# Sheet3.net
KiCad netlist of a schematic drawn in Altium Designer
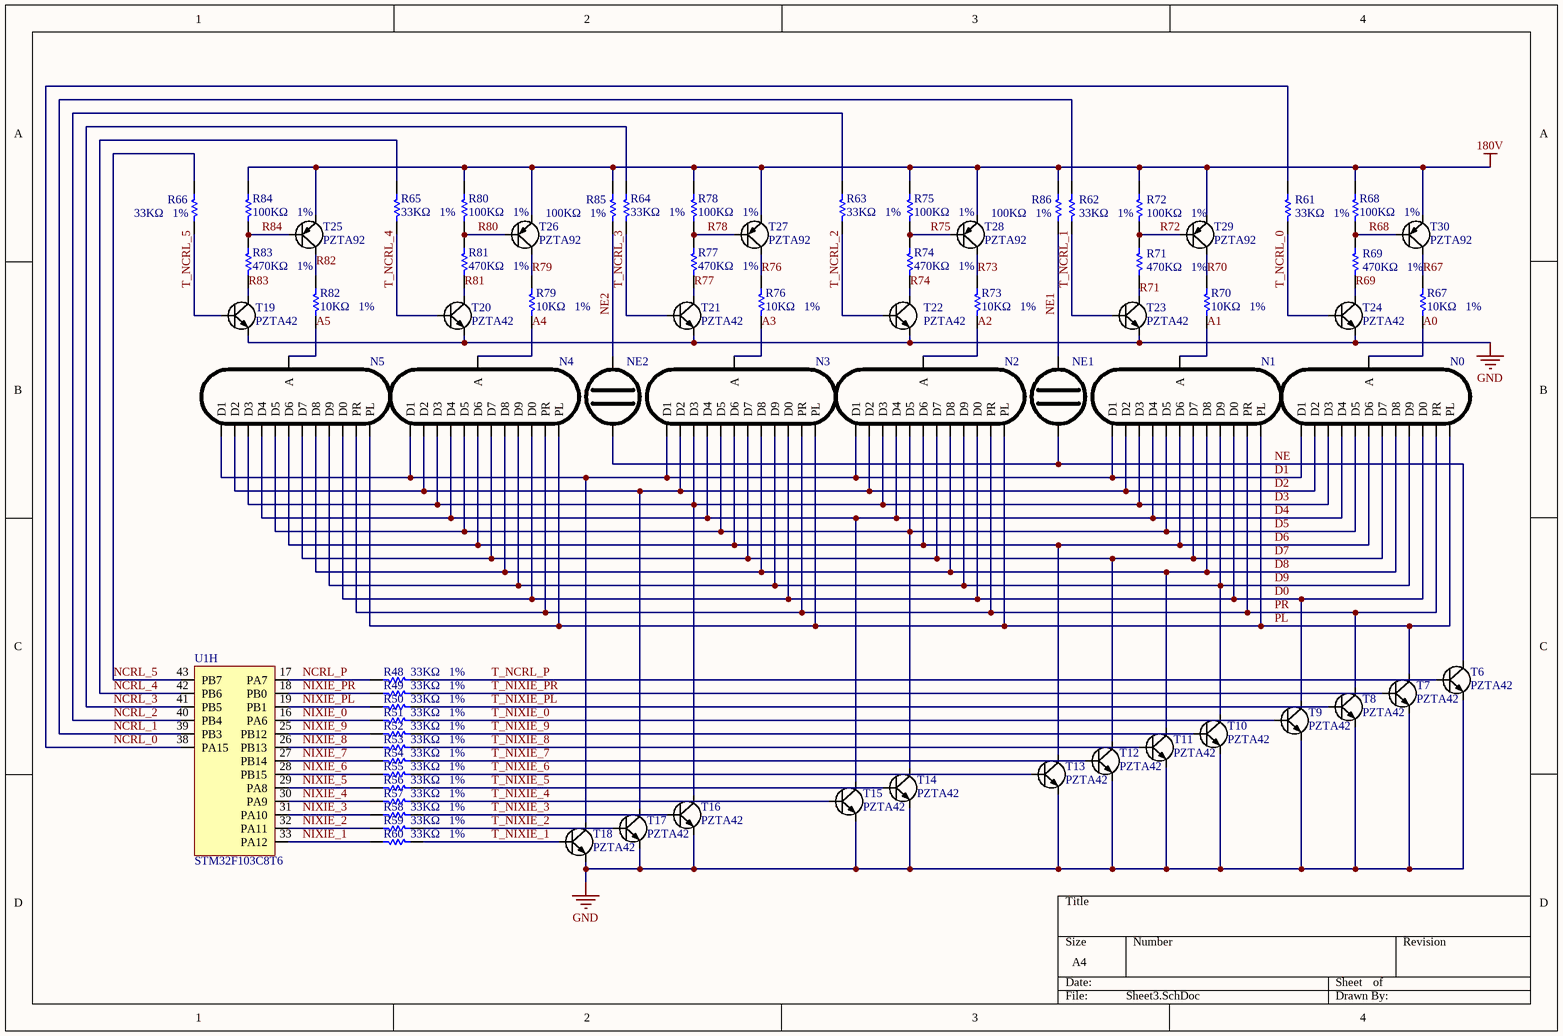
[diagram p0: Sheet3.SchDoc]

(export (version "E")
  (design (tool "Eeschema 10.0.6"))
  (components
    (comp (ref "N0")
      (value "NIXIE-IN14")
      (footprint "NIXIE_IN-14")
      (libsource (lib "Nixielib") (part "NIXIE-IN14"))
    )
    (comp (ref "N1")
      (value "NIXIE-IN14")
      (footprint "NIXIE_IN-14")
      (libsource (lib "Nixielib") (part "NIXIE-IN14"))
    )
    (comp (ref "N2")
      (value "NIXIE-IN14")
      (footprint "NIXIE_IN-14")
      (libsource (lib "Nixielib") (part "NIXIE-IN14"))
    )
    (comp (ref "N3")
      (value "NIXIE-IN14")
      (footprint "NIXIE_IN-14")
      (libsource (lib "Nixielib") (part "NIXIE-IN14"))
    )
    (comp (ref "N4")
      (value "NIXIE-IN14")
      (footprint "NIXIE_IN-14")
      (libsource (lib "Nixielib") (part "NIXIE-IN14"))
    )
    (comp (ref "N5")
      (value "NIXIE-IN14")
      (footprint "NIXIE_IN-14")
      (libsource (lib "Nixielib") (part "NIXIE-IN14"))
    )
    (comp (ref "NE1")
      (value "NEON-LAMP")
      (footprint "NIXIE_IN-3")
      (libsource (lib "Nixielib") (part "NEON-LAMP"))
    )
    (comp (ref "NE2")
      (value "NEON-LAMP")
      (footprint "NIXIE_IN-3")
      (libsource (lib "Nixielib") (part "NEON-LAMP"))
    )
    (comp (ref "R48") (value "33KΩ   1%") (footprint "0603") (libsource (lib "Nixielib") (part "RES")))
    (comp (ref "R49") (value "33KΩ   1%") (footprint "0603") (libsource (lib "Nixielib") (part "RES")))
    (comp (ref "R50") (value "33KΩ   1%") (footprint "0603") (libsource (lib "Nixielib") (part "RES")))
    (comp (ref "R51") (value "33KΩ   1%") (footprint "0603") (libsource (lib "Nixielib") (part "RES")))
    (comp (ref "R52") (value "33KΩ   1%") (footprint "0603") (libsource (lib "Nixielib") (part "RES")))
    (comp (ref "R53") (value "33KΩ   1%") (footprint "0603") (libsource (lib "Nixielib") (part "RES")))
    (comp (ref "R54") (value "33KΩ   1%") (footprint "0603") (libsource (lib "Nixielib") (part "RES")))
    (comp (ref "R55") (value "33KΩ   1%") (footprint "0603") (libsource (lib "Nixielib") (part "RES")))
    (comp (ref "R56") (value "33KΩ   1%") (footprint "0603") (libsource (lib "Nixielib") (part "RES")))
    (comp (ref "R57") (value "33KΩ   1%") (footprint "0603") (libsource (lib "Nixielib") (part "RES")))
    (comp (ref "R58") (value "33KΩ   1%") (footprint "0603") (libsource (lib "Nixielib") (part "RES")))
    (comp (ref "R59") (value "33KΩ   1%") (footprint "0603") (libsource (lib "Nixielib") (part "RES")))
    (comp (ref "R60") (value "33KΩ   1%") (footprint "0603") (libsource (lib "Nixielib") (part "RES")))
    (comp (ref "R61") (value "33KΩ   1%") (footprint "0603") (libsource (lib "Nixielib") (part "RES")))
    (comp (ref "R62") (value "33KΩ   1%") (footprint "0603") (libsource (lib "Nixielib") (part "RES")))
    (comp (ref "R63") (value "33KΩ   1%") (footprint "0603") (libsource (lib "Nixielib") (part "RES")))
    (comp (ref "R64") (value "33KΩ   1%") (footprint "0603") (libsource (lib "Nixielib") (part "RES")))
    (comp (ref "R65") (value "33KΩ   1%") (footprint "0603") (libsource (lib "Nixielib") (part "RES")))
    (comp (ref "R66") (value "33KΩ   1%") (footprint "0603") (libsource (lib "Nixielib") (part "RES")))
    (comp (ref "R67") (value "10KΩ   1%") (footprint "0603") (libsource (lib "Nixielib") (part "RES")))
    (comp (ref "R68") (value "100KΩ   1%") (footprint "0603") (libsource (lib "Nixielib") (part "RES")))
    (comp (ref "R69") (value "470KΩ   1%") (footprint "0603") (libsource (lib "Nixielib") (part "RES")))
    (comp (ref "R70") (value "10KΩ   1%") (footprint "0603") (libsource (lib "Nixielib") (part "RES")))
    (comp (ref "R71") (value "470KΩ   1%") (footprint "0603") (libsource (lib "Nixielib") (part "RES")))
    (comp (ref "R72") (value "100KΩ   1%") (footprint "0603") (libsource (lib "Nixielib") (part "RES")))
    (comp (ref "R73") (value "10KΩ   1%") (footprint "0603") (libsource (lib "Nixielib") (part "RES")))
    (comp (ref "R74") (value "470KΩ   1%") (footprint "0603") (libsource (lib "Nixielib") (part "RES")))
    (comp (ref "R75") (value "100KΩ   1%") (footprint "0603") (libsource (lib "Nixielib") (part "RES")))
    (comp (ref "R76") (value "10KΩ   1%") (footprint "0603") (libsource (lib "Nixielib") (part "RES")))
    (comp (ref "R77") (value "470KΩ   1%") (footprint "0603") (libsource (lib "Nixielib") (part "RES")))
    (comp (ref "R78") (value "100KΩ   1%") (footprint "0603") (libsource (lib "Nixielib") (part "RES")))
    (comp (ref "R79") (value "10KΩ   1%") (footprint "0603") (libsource (lib "Nixielib") (part "RES")))
    (comp (ref "R80") (value "100KΩ   1%") (footprint "0603") (libsource (lib "Nixielib") (part "RES")))
    (comp (ref "R81") (value "470KΩ   1%") (footprint "0603") (libsource (lib "Nixielib") (part "RES")))
    (comp (ref "R82") (value "10KΩ   1%") (footprint "0603") (libsource (lib "Nixielib") (part "RES")))
    (comp (ref "R83") (value "470KΩ   1%") (footprint "0603") (libsource (lib "Nixielib") (part "RES")))
    (comp (ref "R84") (value "100KΩ   1%") (footprint "0603") (libsource (lib "Nixielib") (part "RES")))
    (comp (ref "R85") (value "100KΩ   1%") (footprint "0603") (libsource (lib "Nixielib") (part "RES")))
    (comp (ref "R86") (value "100KΩ   1%") (footprint "0603") (libsource (lib "Nixielib") (part "RES")))
    (comp (ref "T6") (value "PZTA42") (footprint "SOT-23") (libsource (lib "Nixielib") (part "NPN")))
    (comp (ref "T7") (value "PZTA42") (footprint "SOT-23") (libsource (lib "Nixielib") (part "NPN")))
    (comp (ref "T8") (value "PZTA42") (footprint "SOT-23") (libsource (lib "Nixielib") (part "NPN")))
    (comp (ref "T9") (value "PZTA42") (footprint "SOT-23") (libsource (lib "Nixielib") (part "NPN")))
    (comp (ref "T10") (value "PZTA42") (footprint "SOT-23") (libsource (lib "Nixielib") (part "NPN")))
    (comp (ref "T11") (value "PZTA42") (footprint "SOT-23") (libsource (lib "Nixielib") (part "NPN")))
    (comp (ref "T12") (value "PZTA42") (footprint "SOT-23") (libsource (lib "Nixielib") (part "NPN")))
    (comp (ref "T13") (value "PZTA42") (footprint "SOT-23") (libsource (lib "Nixielib") (part "NPN")))
    (comp (ref "T14") (value "PZTA42") (footprint "SOT-23") (libsource (lib "Nixielib") (part "NPN")))
    (comp (ref "T15") (value "PZTA42") (footprint "SOT-23") (libsource (lib "Nixielib") (part "NPN")))
    (comp (ref "T16") (value "PZTA42") (footprint "SOT-23") (libsource (lib "Nixielib") (part "NPN")))
    (comp (ref "T17") (value "PZTA42") (footprint "SOT-23") (libsource (lib "Nixielib") (part "NPN")))
    (comp (ref "T18") (value "PZTA42") (footprint "SOT-23") (libsource (lib "Nixielib") (part "NPN")))
    (comp (ref "T19") (value "PZTA42") (footprint "SOT-23") (libsource (lib "Nixielib") (part "NPN")))
    (comp (ref "T20") (value "PZTA42") (footprint "SOT-23") (libsource (lib "Nixielib") (part "NPN")))
    (comp (ref "T21") (value "PZTA42") (footprint "SOT-23") (libsource (lib "Nixielib") (part "NPN")))
    (comp (ref "T22") (value "PZTA42") (footprint "SOT-23") (libsource (lib "Nixielib") (part "NPN")))
    (comp (ref "T23") (value "PZTA42") (footprint "SOT-23") (libsource (lib "Nixielib") (part "NPN")))
    (comp (ref "T24") (value "PZTA42") (footprint "SOT-23") (libsource (lib "Nixielib") (part "NPN")))
    (comp (ref "T25") (value "PZTA92") (footprint "SOT-23") (libsource (lib "Nixielib") (part "PNP")))
    (comp (ref "T26") (value "PZTA92") (footprint "SOT-23") (libsource (lib "Nixielib") (part "PNP")))
    (comp (ref "T27") (value "PZTA92") (footprint "SOT-23") (libsource (lib "Nixielib") (part "PNP")))
    (comp (ref "T28") (value "PZTA92") (footprint "SOT-23") (libsource (lib "Nixielib") (part "PNP")))
    (comp (ref "T29") (value "PZTA92") (footprint "SOT-23") (libsource (lib "Nixielib") (part "PNP")))
    (comp (ref "T30") (value "PZTA92") (footprint "SOT-23") (libsource (lib "Nixielib") (part "PNP")))
    (comp (ref "U1")
      (value "STM32F103C8T6")
      (footprint "LQFP48")
      (libsource (lib "Nixielib") (part "STM32F103C8T6"))
    )
  )
  (nets
    (net (code "1") (name "/A0") (class "Default")
      (node (ref "N0") (pin "1") (pinfunction "A_1") (pintype "passive"))
      (node (ref "R67") (pin "1") (pinfunction "1_1") (pintype "passive"))
    )
    (net (code "2") (name "/A1") (class "Default")
      (node (ref "N1") (pin "1") (pinfunction "A_1") (pintype "passive"))
      (node (ref "R70") (pin "1") (pinfunction "1_1") (pintype "passive"))
    )
    (net (code "3") (name "/A2") (class "Default")
      (node (ref "N2") (pin "1") (pinfunction "A_1") (pintype "passive"))
      (node (ref "R73") (pin "1") (pinfunction "1_1") (pintype "passive"))
    )
    (net (code "4") (name "/A3") (class "Default")
      (node (ref "N3") (pin "1") (pinfunction "A_1") (pintype "passive"))
      (node (ref "R76") (pin "1") (pinfunction "1_1") (pintype "passive"))
    )
    (net (code "5") (name "/A4") (class "Default")
      (node (ref "N4") (pin "1") (pinfunction "A_1") (pintype "passive"))
      (node (ref "R79") (pin "1") (pinfunction "1_1") (pintype "passive"))
    )
    (net (code "6") (name "/A5") (class "Default")
      (node (ref "N5") (pin "1") (pinfunction "A_1") (pintype "passive"))
      (node (ref "R82") (pin "1") (pinfunction "1_1") (pintype "passive"))
    )
    (net (code "7") (name "/D0") (class "Default")
      (node (ref "N0") (pin "12") (pinfunction "D0_12") (pintype "passive"))
      (node (ref "N1") (pin "12") (pinfunction "D0_12") (pintype "passive"))
      (node (ref "N2") (pin "12") (pinfunction "D0_12") (pintype "passive"))
      (node (ref "N3") (pin "12") (pinfunction "D0_12") (pintype "passive"))
      (node (ref "N4") (pin "12") (pinfunction "D0_12") (pintype "passive"))
      (node (ref "N5") (pin "12") (pinfunction "D0_12") (pintype "passive"))
      (node (ref "T9") (pin "3") (pinfunction "C_3") (pintype "passive"))
    )
    (net (code "8") (name "/D1") (class "Default")
      (node (ref "N0") (pin "3") (pinfunction "D1_3") (pintype "passive"))
      (node (ref "N1") (pin "3") (pinfunction "D1_3") (pintype "passive"))
      (node (ref "N2") (pin "3") (pinfunction "D1_3") (pintype "passive"))
      (node (ref "N3") (pin "3") (pinfunction "D1_3") (pintype "passive"))
      (node (ref "N4") (pin "3") (pinfunction "D1_3") (pintype "passive"))
      (node (ref "N5") (pin "3") (pinfunction "D1_3") (pintype "passive"))
      (node (ref "T18") (pin "3") (pinfunction "C_3") (pintype "passive"))
    )
    (net (code "9") (name "/D2") (class "Default")
      (node (ref "N0") (pin "4") (pinfunction "D2_4") (pintype "passive"))
      (node (ref "N1") (pin "4") (pinfunction "D2_4") (pintype "passive"))
      (node (ref "N2") (pin "4") (pinfunction "D2_4") (pintype "passive"))
      (node (ref "N3") (pin "4") (pinfunction "D2_4") (pintype "passive"))
      (node (ref "N4") (pin "4") (pinfunction "D2_4") (pintype "passive"))
      (node (ref "N5") (pin "4") (pinfunction "D2_4") (pintype "passive"))
      (node (ref "T17") (pin "3") (pinfunction "C_3") (pintype "passive"))
    )
    (net (code "10") (name "/D3") (class "Default")
      (node (ref "N0") (pin "5") (pinfunction "D3_5") (pintype "passive"))
      (node (ref "N1") (pin "5") (pinfunction "D3_5") (pintype "passive"))
      (node (ref "N2") (pin "5") (pinfunction "D3_5") (pintype "passive"))
      (node (ref "N3") (pin "5") (pinfunction "D3_5") (pintype "passive"))
      (node (ref "N4") (pin "5") (pinfunction "D3_5") (pintype "passive"))
      (node (ref "N5") (pin "5") (pinfunction "D3_5") (pintype "passive"))
      (node (ref "T16") (pin "3") (pinfunction "C_3") (pintype "passive"))
    )
    (net (code "11") (name "/D4") (class "Default")
      (node (ref "N0") (pin "6") (pinfunction "D4_6") (pintype "passive"))
      (node (ref "N1") (pin "6") (pinfunction "D4_6") (pintype "passive"))
      (node (ref "N2") (pin "6") (pinfunction "D4_6") (pintype "passive"))
      (node (ref "N3") (pin "6") (pinfunction "D4_6") (pintype "passive"))
      (node (ref "N4") (pin "6") (pinfunction "D4_6") (pintype "passive"))
      (node (ref "N5") (pin "6") (pinfunction "D4_6") (pintype "passive"))
      (node (ref "T15") (pin "3") (pinfunction "C_3") (pintype "passive"))
    )
    (net (code "12") (name "/D5") (class "Default")
      (node (ref "N0") (pin "7") (pinfunction "D5_7") (pintype "passive"))
      (node (ref "N1") (pin "7") (pinfunction "D5_7") (pintype "passive"))
      (node (ref "N2") (pin "7") (pinfunction "D5_7") (pintype "passive"))
      (node (ref "N3") (pin "7") (pinfunction "D5_7") (pintype "passive"))
      (node (ref "N4") (pin "7") (pinfunction "D5_7") (pintype "passive"))
      (node (ref "N5") (pin "7") (pinfunction "D5_7") (pintype "passive"))
      (node (ref "T14") (pin "3") (pinfunction "C_3") (pintype "passive"))
    )
    (net (code "13") (name "/D6") (class "Default")
      (node (ref "N0") (pin "8") (pinfunction "D6_8") (pintype "passive"))
      (node (ref "N1") (pin "8") (pinfunction "D6_8") (pintype "passive"))
      (node (ref "N2") (pin "8") (pinfunction "D6_8") (pintype "passive"))
      (node (ref "N3") (pin "8") (pinfunction "D6_8") (pintype "passive"))
      (node (ref "N4") (pin "8") (pinfunction "D6_8") (pintype "passive"))
      (node (ref "N5") (pin "8") (pinfunction "D6_8") (pintype "passive"))
      (node (ref "T13") (pin "3") (pinfunction "C_3") (pintype "passive"))
    )
    (net (code "14") (name "/D7") (class "Default")
      (node (ref "N0") (pin "9") (pinfunction "D7_9") (pintype "passive"))
      (node (ref "N1") (pin "9") (pinfunction "D7_9") (pintype "passive"))
      (node (ref "N2") (pin "9") (pinfunction "D7_9") (pintype "passive"))
      (node (ref "N3") (pin "9") (pinfunction "D7_9") (pintype "passive"))
      (node (ref "N4") (pin "9") (pinfunction "D7_9") (pintype "passive"))
      (node (ref "N5") (pin "9") (pinfunction "D7_9") (pintype "passive"))
      (node (ref "T12") (pin "3") (pinfunction "C_3") (pintype "passive"))
    )
    (net (code "15") (name "/D8") (class "Default")
      (node (ref "N0") (pin "10") (pinfunction "D8_10") (pintype "passive"))
      (node (ref "N1") (pin "10") (pinfunction "D8_10") (pintype "passive"))
      (node (ref "N2") (pin "10") (pinfunction "D8_10") (pintype "passive"))
      (node (ref "N3") (pin "10") (pinfunction "D8_10") (pintype "passive"))
      (node (ref "N4") (pin "10") (pinfunction "D8_10") (pintype "passive"))
      (node (ref "N5") (pin "10") (pinfunction "D8_10") (pintype "passive"))
      (node (ref "T11") (pin "3") (pinfunction "C_3") (pintype "passive"))
    )
    (net (code "16") (name "/D9") (class "Default")
      (node (ref "N0") (pin "11") (pinfunction "D9_11") (pintype "passive"))
      (node (ref "N1") (pin "11") (pinfunction "D9_11") (pintype "passive"))
      (node (ref "N2") (pin "11") (pinfunction "D9_11") (pintype "passive"))
      (node (ref "N3") (pin "11") (pinfunction "D9_11") (pintype "passive"))
      (node (ref "N4") (pin "11") (pinfunction "D9_11") (pintype "passive"))
      (node (ref "N5") (pin "11") (pinfunction "D9_11") (pintype "passive"))
      (node (ref "T10") (pin "3") (pinfunction "C_3") (pintype "passive"))
    )
    (net (code "17") (name "/NCRL_0") (class "Default")
      (node (ref "R61") (pin "1") (pinfunction "1_1") (pintype "passive"))
      (node (ref "U1") (pin "38") (pinfunction "PA15_38") (pintype "passive"))
    )
    (net (code "18") (name "/NCRL_1") (class "Default")
      (node (ref "R62") (pin "2") (pinfunction "2_2") (pintype "passive"))
      (node (ref "U1") (pin "39") (pinfunction "PB3_39") (pintype "passive"))
    )
    (net (code "19") (name "/NCRL_2") (class "Default")
      (node (ref "R63") (pin "2") (pinfunction "2_2") (pintype "passive"))
      (node (ref "U1") (pin "40") (pinfunction "PB4_40") (pintype "passive"))
    )
    (net (code "20") (name "/NCRL_3") (class "Default")
      (node (ref "R64") (pin "1") (pinfunction "1_1") (pintype "passive"))
      (node (ref "U1") (pin "41") (pinfunction "PB5_41") (pintype "passive"))
    )
    (net (code "21") (name "/NCRL_4") (class "Default")
      (node (ref "R65") (pin "2") (pinfunction "2_2") (pintype "passive"))
      (node (ref "U1") (pin "42") (pinfunction "PB6_42") (pintype "passive"))
    )
    (net (code "22") (name "/NCRL_5") (class "Default")
      (node (ref "R66") (pin "2") (pinfunction "2_2") (pintype "passive"))
      (node (ref "U1") (pin "43") (pinfunction "PB7_43") (pintype "passive"))
    )
    (net (code "23") (name "/NCRL_P") (class "Default")
      (node (ref "R48") (pin "1") (pinfunction "1_1") (pintype "passive"))
      (node (ref "U1") (pin "17") (pinfunction "PA7_17") (pintype "passive"))
    )
    (net (code "24") (name "/NE") (class "Default")
      (node (ref "NE1") (pin "2") (pinfunction "2_2") (pintype "passive"))
      (node (ref "NE2") (pin "2") (pinfunction "2_2") (pintype "passive"))
      (node (ref "T6") (pin "3") (pinfunction "C_3") (pintype "passive"))
    )
    (net (code "25") (name "/NE1") (class "Default")
      (node (ref "NE1") (pin "1") (pinfunction "1_1") (pintype "passive"))
      (node (ref "R86") (pin "1") (pinfunction "1_1") (pintype "passive"))
    )
    (net (code "26") (name "/NE2") (class "Default")
      (node (ref "NE2") (pin "1") (pinfunction "1_1") (pintype "passive"))
      (node (ref "R85") (pin "1") (pinfunction "1_1") (pintype "passive"))
    )
    (net (code "27") (name "/NIXIE_0") (class "Default")
      (node (ref "R51") (pin "1") (pinfunction "1_1") (pintype "passive"))
      (node (ref "U1") (pin "16") (pinfunction "PA6_16") (pintype "passive"))
    )
    (net (code "28") (name "/NIXIE_1") (class "Default")
      (node (ref "R60") (pin "1") (pinfunction "1_1") (pintype "passive"))
      (node (ref "U1") (pin "33") (pinfunction "PA12_33") (pintype "passive"))
    )
    (net (code "29") (name "/NIXIE_2") (class "Default")
      (node (ref "R59") (pin "1") (pinfunction "1_1") (pintype "passive"))
      (node (ref "U1") (pin "32") (pinfunction "PA11_32") (pintype "passive"))
    )
    (net (code "30") (name "/NIXIE_3") (class "Default")
      (node (ref "R58") (pin "1") (pinfunction "1_1") (pintype "passive"))
      (node (ref "U1") (pin "31") (pinfunction "PA10_31") (pintype "passive"))
    )
    (net (code "31") (name "/NIXIE_4") (class "Default")
      (node (ref "R57") (pin "1") (pinfunction "1_1") (pintype "passive"))
      (node (ref "U1") (pin "30") (pinfunction "PA9_30") (pintype "passive"))
    )
    (net (code "32") (name "/NIXIE_5") (class "Default")
      (node (ref "R56") (pin "1") (pinfunction "1_1") (pintype "passive"))
      (node (ref "U1") (pin "29") (pinfunction "PA8_29") (pintype "passive"))
    )
    (net (code "33") (name "/NIXIE_6") (class "Default")
      (node (ref "R55") (pin "1") (pinfunction "1_1") (pintype "passive"))
      (node (ref "U1") (pin "28") (pinfunction "PB15_28") (pintype "passive"))
    )
    (net (code "34") (name "/NIXIE_7") (class "Default")
      (node (ref "R54") (pin "1") (pinfunction "1_1") (pintype "passive"))
      (node (ref "U1") (pin "27") (pinfunction "PB14_27") (pintype "passive"))
    )
    (net (code "35") (name "/NIXIE_8") (class "Default")
      (node (ref "R53") (pin "1") (pinfunction "1_1") (pintype "passive"))
      (node (ref "U1") (pin "26") (pinfunction "PB13_26") (pintype "passive"))
    )
    (net (code "36") (name "/NIXIE_9") (class "Default")
      (node (ref "R52") (pin "1") (pinfunction "1_1") (pintype "passive"))
      (node (ref "U1") (pin "25") (pinfunction "PB12_25") (pintype "passive"))
    )
    (net (code "37") (name "/NIXIE_PL") (class "Default")
      (node (ref "R50") (pin "1") (pinfunction "1_1") (pintype "passive"))
      (node (ref "U1") (pin "19") (pinfunction "PB1_19") (pintype "passive"))
    )
    (net (code "38") (name "/NIXIE_PR") (class "Default")
      (node (ref "R49") (pin "1") (pinfunction "1_1") (pintype "passive"))
      (node (ref "U1") (pin "18") (pinfunction "PB0_18") (pintype "passive"))
    )
    (net (code "39") (name "/PL") (class "Default")
      (node (ref "N0") (pin "2") (pinfunction "PL_2") (pintype "passive"))
      (node (ref "N1") (pin "2") (pinfunction "PL_2") (pintype "passive"))
      (node (ref "N2") (pin "2") (pinfunction "PL_2") (pintype "passive"))
      (node (ref "N3") (pin "2") (pinfunction "PL_2") (pintype "passive"))
      (node (ref "N4") (pin "2") (pinfunction "PL_2") (pintype "passive"))
      (node (ref "N5") (pin "2") (pinfunction "PL_2") (pintype "passive"))
      (node (ref "T7") (pin "3") (pinfunction "C_3") (pintype "passive"))
    )
    (net (code "40") (name "/PR") (class "Default")
      (node (ref "N0") (pin "13") (pinfunction "PR_13") (pintype "passive"))
      (node (ref "N1") (pin "13") (pinfunction "PR_13") (pintype "passive"))
      (node (ref "N2") (pin "13") (pinfunction "PR_13") (pintype "passive"))
      (node (ref "N3") (pin "13") (pinfunction "PR_13") (pintype "passive"))
      (node (ref "N4") (pin "13") (pinfunction "PR_13") (pintype "passive"))
      (node (ref "N5") (pin "13") (pinfunction "PR_13") (pintype "passive"))
      (node (ref "T8") (pin "3") (pinfunction "C_3") (pintype "passive"))
    )
    (net (code "41") (name "/R67") (class "Default")
      (node (ref "R67") (pin "2") (pinfunction "2_2") (pintype "passive"))
      (node (ref "T30") (pin "3") (pinfunction "C_3") (pintype "passive"))
    )
    (net (code "42") (name "/R68") (class "Default")
      (node (ref "R68") (pin "1") (pinfunction "1_1") (pintype "passive"))
      (node (ref "R69") (pin "2") (pinfunction "2_2") (pintype "passive"))
      (node (ref "T30") (pin "1") (pinfunction "B_1") (pintype "passive"))
    )
    (net (code "43") (name "/R69") (class "Default")
      (node (ref "R69") (pin "1") (pinfunction "1_1") (pintype "passive"))
      (node (ref "T24") (pin "3") (pinfunction "C_3") (pintype "passive"))
    )
    (net (code "44") (name "/R70") (class "Default")
      (node (ref "R70") (pin "2") (pinfunction "2_2") (pintype "passive"))
      (node (ref "T29") (pin "3") (pinfunction "C_3") (pintype "passive"))
    )
    (net (code "45") (name "/R71") (class "Default")
      (node (ref "R71") (pin "1") (pinfunction "1_1") (pintype "passive"))
      (node (ref "T23") (pin "3") (pinfunction "C_3") (pintype "passive"))
    )
    (net (code "46") (name "/R72") (class "Default")
      (node (ref "R71") (pin "2") (pinfunction "2_2") (pintype "passive"))
      (node (ref "R72") (pin "1") (pinfunction "1_1") (pintype "passive"))
      (node (ref "T29") (pin "1") (pinfunction "B_1") (pintype "passive"))
    )
    (net (code "47") (name "/R73") (class "Default")
      (node (ref "R73") (pin "2") (pinfunction "2_2") (pintype "passive"))
      (node (ref "T28") (pin "3") (pinfunction "C_3") (pintype "passive"))
    )
    (net (code "48") (name "/R74") (class "Default")
      (node (ref "R74") (pin "1") (pinfunction "1_1") (pintype "passive"))
      (node (ref "T22") (pin "3") (pinfunction "C_3") (pintype "passive"))
    )
    (net (code "49") (name "/R75") (class "Default")
      (node (ref "R74") (pin "2") (pinfunction "2_2") (pintype "passive"))
      (node (ref "R75") (pin "1") (pinfunction "1_1") (pintype "passive"))
      (node (ref "T28") (pin "1") (pinfunction "B_1") (pintype "passive"))
    )
    (net (code "50") (name "/R76") (class "Default")
      (node (ref "R76") (pin "2") (pinfunction "2_2") (pintype "passive"))
      (node (ref "T27") (pin "3") (pinfunction "C_3") (pintype "passive"))
    )
    (net (code "51") (name "/R77") (class "Default")
      (node (ref "R77") (pin "1") (pinfunction "1_1") (pintype "passive"))
      (node (ref "T21") (pin "3") (pinfunction "C_3") (pintype "passive"))
    )
    (net (code "52") (name "/R78") (class "Default")
      (node (ref "R77") (pin "2") (pinfunction "2_2") (pintype "passive"))
      (node (ref "R78") (pin "1") (pinfunction "1_1") (pintype "passive"))
      (node (ref "T27") (pin "1") (pinfunction "B_1") (pintype "passive"))
    )
    (net (code "53") (name "/R79") (class "Default")
      (node (ref "R79") (pin "2") (pinfunction "2_2") (pintype "passive"))
      (node (ref "T26") (pin "3") (pinfunction "C_3") (pintype "passive"))
    )
    (net (code "54") (name "/R80") (class "Default")
      (node (ref "R80") (pin "1") (pinfunction "1_1") (pintype "passive"))
      (node (ref "R81") (pin "2") (pinfunction "2_2") (pintype "passive"))
      (node (ref "T26") (pin "1") (pinfunction "B_1") (pintype "passive"))
    )
    (net (code "55") (name "/R81") (class "Default")
      (node (ref "R81") (pin "1") (pinfunction "1_1") (pintype "passive"))
      (node (ref "T20") (pin "3") (pinfunction "C_3") (pintype "passive"))
    )
    (net (code "56") (name "/R82") (class "Default")
      (node (ref "R82") (pin "2") (pinfunction "2_2") (pintype "passive"))
      (node (ref "T25") (pin "3") (pinfunction "C_3") (pintype "passive"))
    )
    (net (code "57") (name "/R83") (class "Default")
      (node (ref "R83") (pin "1") (pinfunction "1_1") (pintype "passive"))
      (node (ref "T19") (pin "3") (pinfunction "C_3") (pintype "passive"))
    )
    (net (code "58") (name "/R84") (class "Default")
      (node (ref "R83") (pin "2") (pinfunction "2_2") (pintype "passive"))
      (node (ref "R84") (pin "1") (pinfunction "1_1") (pintype "passive"))
      (node (ref "T25") (pin "1") (pinfunction "B_1") (pintype "passive"))
    )
    (net (code "59") (name "/T_NCRL_0") (class "Default")
      (node (ref "R61") (pin "2") (pinfunction "2_2") (pintype "passive"))
      (node (ref "T24") (pin "1") (pinfunction "B_1") (pintype "passive"))
    )
    (net (code "60") (name "/T_NCRL_1") (class "Default")
      (node (ref "R62") (pin "1") (pinfunction "1_1") (pintype "passive"))
      (node (ref "T23") (pin "1") (pinfunction "B_1") (pintype "passive"))
    )
    (net (code "61") (name "/T_NCRL_2") (class "Default")
      (node (ref "R63") (pin "1") (pinfunction "1_1") (pintype "passive"))
      (node (ref "T22") (pin "1") (pinfunction "B_1") (pintype "passive"))
    )
    (net (code "62") (name "/T_NCRL_3") (class "Default")
      (node (ref "R64") (pin "2") (pinfunction "2_2") (pintype "passive"))
      (node (ref "T21") (pin "1") (pinfunction "B_1") (pintype "passive"))
    )
    (net (code "63") (name "/T_NCRL_4") (class "Default")
      (node (ref "R65") (pin "1") (pinfunction "1_1") (pintype "passive"))
      (node (ref "T20") (pin "1") (pinfunction "B_1") (pintype "passive"))
    )
    (net (code "64") (name "/T_NCRL_5") (class "Default")
      (node (ref "R66") (pin "1") (pinfunction "1_1") (pintype "passive"))
      (node (ref "T19") (pin "1") (pinfunction "B_1") (pintype "passive"))
    )
    (net (code "65") (name "/T_NCRL_P") (class "Default")
      (node (ref "R48") (pin "2") (pinfunction "2_2") (pintype "passive"))
      (node (ref "T6") (pin "1") (pinfunction "B_1") (pintype "passive"))
    )
    (net (code "66") (name "/T_NIXIE_0") (class "Default")
      (node (ref "R51") (pin "2") (pinfunction "2_2") (pintype "passive"))
      (node (ref "T9") (pin "1") (pinfunction "B_1") (pintype "passive"))
    )
    (net (code "67") (name "/T_NIXIE_1") (class "Default")
      (node (ref "R60") (pin "2") (pinfunction "2_2") (pintype "passive"))
      (node (ref "T18") (pin "1") (pinfunction "B_1") (pintype "passive"))
    )
    (net (code "68") (name "/T_NIXIE_2") (class "Default")
      (node (ref "R59") (pin "2") (pinfunction "2_2") (pintype "passive"))
      (node (ref "T17") (pin "1") (pinfunction "B_1") (pintype "passive"))
    )
    (net (code "69") (name "/T_NIXIE_3") (class "Default")
      (node (ref "R58") (pin "2") (pinfunction "2_2") (pintype "passive"))
      (node (ref "T16") (pin "1") (pinfunction "B_1") (pintype "passive"))
    )
    (net (code "70") (name "/T_NIXIE_4") (class "Default")
      (node (ref "R57") (pin "2") (pinfunction "2_2") (pintype "passive"))
      (node (ref "T15") (pin "1") (pinfunction "B_1") (pintype "passive"))
    )
    (net (code "71") (name "/T_NIXIE_5") (class "Default")
      (node (ref "R56") (pin "2") (pinfunction "2_2") (pintype "passive"))
      (node (ref "T14") (pin "1") (pinfunction "B_1") (pintype "passive"))
    )
    (net (code "72") (name "/T_NIXIE_6") (class "Default")
      (node (ref "R55") (pin "2") (pinfunction "2_2") (pintype "passive"))
      (node (ref "T13") (pin "1") (pinfunction "B_1") (pintype "passive"))
    )
    (net (code "73") (name "/T_NIXIE_7") (class "Default")
      (node (ref "R54") (pin "2") (pinfunction "2_2") (pintype "passive"))
      (node (ref "T12") (pin "1") (pinfunction "B_1") (pintype "passive"))
    )
    (net (code "74") (name "/T_NIXIE_8") (class "Default")
      (node (ref "R53") (pin "2") (pinfunction "2_2") (pintype "passive"))
      (node (ref "T11") (pin "1") (pinfunction "B_1") (pintype "passive"))
    )
    (net (code "75") (name "/T_NIXIE_9") (class "Default")
      (node (ref "R52") (pin "2") (pinfunction "2_2") (pintype "passive"))
      (node (ref "T10") (pin "1") (pinfunction "B_1") (pintype "passive"))
    )
    (net (code "76") (name "/T_NIXIE_PL") (class "Default")
      (node (ref "R50") (pin "2") (pinfunction "2_2") (pintype "passive"))
      (node (ref "T8") (pin "1") (pinfunction "B_1") (pintype "passive"))
    )
    (net (code "77") (name "/T_NIXIE_PR") (class "Default")
      (node (ref "R49") (pin "2") (pinfunction "2_2") (pintype "passive"))
      (node (ref "T7") (pin "1") (pinfunction "B_1") (pintype "passive"))
    )
    (net (code "78") (name "180V") (class "Default")
      (node (ref "R68") (pin "2") (pinfunction "2_2") (pintype "passive"))
      (node (ref "R72") (pin "2") (pinfunction "2_2") (pintype "passive"))
      (node (ref "R75") (pin "2") (pinfunction "2_2") (pintype "passive"))
      (node (ref "R78") (pin "2") (pinfunction "2_2") (pintype "passive"))
      (node (ref "R80") (pin "2") (pinfunction "2_2") (pintype "passive"))
      (node (ref "R84") (pin "2") (pinfunction "2_2") (pintype "passive"))
      (node (ref "R85") (pin "2") (pinfunction "2_2") (pintype "passive"))
      (node (ref "R86") (pin "2") (pinfunction "2_2") (pintype "passive"))
      (node (ref "T25") (pin "2") (pinfunction "E_2") (pintype "passive"))
      (node (ref "T26") (pin "2") (pinfunction "E_2") (pintype "passive"))
      (node (ref "T27") (pin "2") (pinfunction "E_2") (pintype "passive"))
      (node (ref "T28") (pin "2") (pinfunction "E_2") (pintype "passive"))
      (node (ref "T29") (pin "2") (pinfunction "E_2") (pintype "passive"))
      (node (ref "T30") (pin "2") (pinfunction "E_2") (pintype "passive"))
    )
    (net (code "79") (name "GND") (class "Default")
      (node (ref "T10") (pin "2") (pinfunction "E_2") (pintype "passive"))
      (node (ref "T11") (pin "2") (pinfunction "E_2") (pintype "passive"))
      (node (ref "T12") (pin "2") (pinfunction "E_2") (pintype "passive"))
      (node (ref "T13") (pin "2") (pinfunction "E_2") (pintype "passive"))
      (node (ref "T14") (pin "2") (pinfunction "E_2") (pintype "passive"))
      (node (ref "T15") (pin "2") (pinfunction "E_2") (pintype "passive"))
      (node (ref "T16") (pin "2") (pinfunction "E_2") (pintype "passive"))
      (node (ref "T17") (pin "2") (pinfunction "E_2") (pintype "passive"))
      (node (ref "T18") (pin "2") (pinfunction "E_2") (pintype "passive"))
      (node (ref "T19") (pin "2") (pinfunction "E_2") (pintype "passive"))
      (node (ref "T20") (pin "2") (pinfunction "E_2") (pintype "passive"))
      (node (ref "T21") (pin "2") (pinfunction "E_2") (pintype "passive"))
      (node (ref "T22") (pin "2") (pinfunction "E_2") (pintype "passive"))
      (node (ref "T23") (pin "2") (pinfunction "E_2") (pintype "passive"))
      (node (ref "T24") (pin "2") (pinfunction "E_2") (pintype "passive"))
      (node (ref "T6") (pin "2") (pinfunction "E_2") (pintype "passive"))
      (node (ref "T7") (pin "2") (pinfunction "E_2") (pintype "passive"))
      (node (ref "T8") (pin "2") (pinfunction "E_2") (pintype "passive"))
      (node (ref "T9") (pin "2") (pinfunction "E_2") (pintype "passive"))
    )
  )
)
